# GateCVBooster.net
KiCad netlist of a schematic drawn in EAGLE
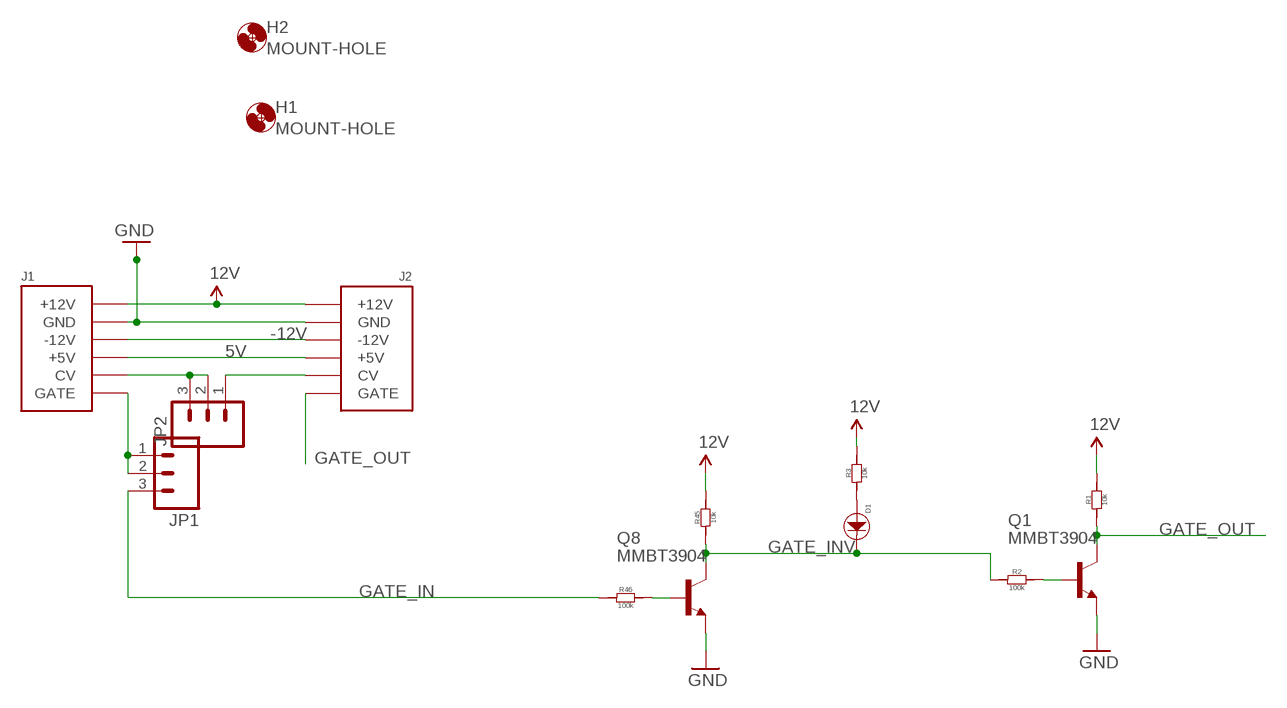
[diagram p0: schematic, sheet 1]

(export (version "E")
  (design (tool "Eeschema 10.0.6"))
  (components
    (comp (ref "D1")
      (value "LED")
      (footprint "eagle-import:LED0603")
      (libsource (lib "eagle-import") (part "LED"))
    )
    (comp (ref "H1")
      (value "MOUNT-HOLE")
      (footprint "eagle-import:3.2-NOMARKINGS-SMALLSAFEZONE")
      (libsource (lib "eagle-import") (part "MOUNT-HOLE"))
    )
    (comp (ref "H2")
      (value "MOUNT-HOLE")
      (footprint "eagle-import:3.2-NOMARKINGS-SMALLSAFEZONE")
      (libsource (lib "eagle-import") (part "MOUNT-HOLE"))
    )
    (comp (ref "J1")
      (value "POWERSHROUDED")
      (footprint "eagle-import:POWER_16_SHROUDED")
      (libsource (lib "eagle-import") (part "POWERSHROUDED"))
    )
    (comp (ref "J2")
      (value "POWER_SHROUDED_NOTEXT")
      (footprint "eagle-import:POWER_16_SHROUDED_NOTEXT")
      (libsource (lib "eagle-import") (part "POWER_SHROUDED_NOTEXT"))
    )
    (comp (ref "JP1")
      (value "M03PTH")
      (footprint "eagle-import:1X03")
      (libsource (lib "eagle-import") (part "M03PTH"))
    )
    (comp (ref "JP2")
      (value "M03PTH")
      (footprint "eagle-import:1X03")
      (libsource (lib "eagle-import") (part "M03PTH"))
    )
    (comp (ref "Q1")
      (value "MMBT3904")
      (footprint "eagle-import:SOT23-BEC")
      (fields (field (name "MF") "NXP") (field (name "MPN") "PMBT3904,215"))
      (libsource (lib "eagle-import") (part "-NPN-SOT23-BECMMBT3904LT1"))
    )
    (comp (ref "Q8")
      (value "MMBT3904")
      (footprint "eagle-import:SOT23-BEC")
      (fields (field (name "MF") "NXP") (field (name "MPN") "PMBT3904,215"))
      (libsource (lib "eagle-import") (part "-NPN-SOT23-BECMMBT3904LT1"))
    )
    (comp (ref "R1")
      (value "10k")
      (footprint "eagle-import:R0603")
      (libsource (lib "eagle-import") (part "R-0603"))
    )
    (comp (ref "R2")
      (value "100k")
      (footprint "eagle-import:R0603")
      (libsource (lib "eagle-import") (part "R-0603"))
    )
    (comp (ref "R3")
      (value "10k")
      (footprint "eagle-import:R0603")
      (libsource (lib "eagle-import") (part "R-0603"))
    )
    (comp (ref "R45")
      (value "10k")
      (footprint "eagle-import:R0603")
      (libsource (lib "eagle-import") (part "R-0603"))
    )
    (comp (ref "R46")
      (value "100k")
      (footprint "eagle-import:R0603")
      (libsource (lib "eagle-import") (part "R-0603"))
    )
  )
  (nets
    (net (code "1") (name "/-12V") (class "Default")
      (node (ref "J1") (pin "1") (pinfunction "-12V_1") (pintype "bidirectional"))
      (node (ref "J1") (pin "2") (pinfunction "-12V_2") (pintype "bidirectional"))
      (node (ref "J2") (pin "1") (pinfunction "-12V_1") (pintype "bidirectional"))
      (node (ref "J2") (pin "2") (pinfunction "-12V_2") (pintype "bidirectional"))
    )
    (net (code "2") (name "/5V") (class "Default")
      (node (ref "J1") (pin "11") (pinfunction "+5V_11") (pintype "bidirectional"))
      (node (ref "J1") (pin "12") (pinfunction "+5V_12") (pintype "bidirectional"))
      (node (ref "J2") (pin "11") (pinfunction "+5V_11") (pintype "bidirectional"))
      (node (ref "J2") (pin "12") (pinfunction "+5V_12") (pintype "bidirectional"))
    )
    (net (code "3") (name "/GATE_IN") (class "Default")
      (node (ref "JP1") (pin "3") (pinfunction "3_3") (pintype "passive"))
      (node (ref "R46") (pin "1") (pinfunction "1_1") (pintype "bidirectional"))
    )
    (net (code "4") (name "/GATE_INV") (class "Default")
      (node (ref "D1") (pin "-") (pinfunction "-_-") (pintype "passive"))
      (node (ref "Q8") (pin "C") (pinfunction "C_C") (pintype "passive"))
      (node (ref "R2") (pin "1") (pinfunction "1_1") (pintype "bidirectional"))
      (node (ref "R45") (pin "1") (pinfunction "1_1") (pintype "bidirectional"))
    )
    (net (code "5") (name "/GATE_OUT") (class "Default")
      (node (ref "J2") (pin "15") (pinfunction "GATE_15") (pintype "bidirectional"))
      (node (ref "J2") (pin "16") (pinfunction "GATE_16") (pintype "bidirectional"))
      (node (ref "Q1") (pin "C") (pinfunction "C_C") (pintype "passive"))
      (node (ref "R1") (pin "1") (pinfunction "1_1") (pintype "bidirectional"))
    )
    (net (code "6") (name "12V") (class "Default")
      (node (ref "J1") (pin "10") (pinfunction "+12V_10") (pintype "bidirectional"))
      (node (ref "J1") (pin "9") (pinfunction "+12V_9") (pintype "bidirectional"))
      (node (ref "J2") (pin "10") (pinfunction "+12V_10") (pintype "bidirectional"))
      (node (ref "J2") (pin "9") (pinfunction "+12V_9") (pintype "bidirectional"))
      (node (ref "R1") (pin "2") (pinfunction "2_2") (pintype "bidirectional"))
      (node (ref "R3") (pin "2") (pinfunction "2_2") (pintype "bidirectional"))
      (node (ref "R45") (pin "2") (pinfunction "2_2") (pintype "bidirectional"))
    )
    (net (code "7") (name "GND") (class "Default")
      (node (ref "J1") (pin "3") (pinfunction "GND_3") (pintype "bidirectional"))
      (node (ref "J1") (pin "4") (pinfunction "GND_4") (pintype "bidirectional"))
      (node (ref "J1") (pin "5") (pinfunction "GND_5") (pintype "bidirectional"))
      (node (ref "J1") (pin "6") (pinfunction "GND_6") (pintype "bidirectional"))
      (node (ref "J1") (pin "7") (pinfunction "GND_7") (pintype "bidirectional"))
      (node (ref "J1") (pin "8") (pinfunction "GND_8") (pintype "bidirectional"))
      (node (ref "J2") (pin "3") (pinfunction "GND_3") (pintype "bidirectional"))
      (node (ref "J2") (pin "4") (pinfunction "GND_4") (pintype "bidirectional"))
      (node (ref "J2") (pin "5") (pinfunction "GND_5") (pintype "bidirectional"))
      (node (ref "J2") (pin "6") (pinfunction "GND_6") (pintype "bidirectional"))
      (node (ref "J2") (pin "7") (pinfunction "GND_7") (pintype "bidirectional"))
      (node (ref "J2") (pin "8") (pinfunction "GND_8") (pintype "bidirectional"))
      (node (ref "Q1") (pin "E") (pinfunction "E_E") (pintype "passive"))
      (node (ref "Q8") (pin "E") (pinfunction "E_E") (pintype "passive"))
    )
    (net (code "8") (name "Net-(D1-Pad+)") (class "Default")
      (node (ref "D1") (pin "+") (pinfunction "+_+") (pintype "passive"))
      (node (ref "R3") (pin "1") (pinfunction "1_1") (pintype "bidirectional"))
    )
    (net (code "9") (name "Net-(J1-CV-Pad13)") (class "Default")
      (node (ref "J1") (pin "13") (pinfunction "CV_13") (pintype "bidirectional"))
      (node (ref "J1") (pin "14") (pinfunction "CV_14") (pintype "bidirectional"))
      (node (ref "JP2") (pin "2") (pinfunction "2_2") (pintype "passive"))
      (node (ref "JP2") (pin "3") (pinfunction "3_3") (pintype "passive"))
    )
    (net (code "10") (name "Net-(J1-GATE-Pad15)") (class "Default")
      (node (ref "J1") (pin "15") (pinfunction "GATE_15") (pintype "bidirectional"))
      (node (ref "J1") (pin "16") (pinfunction "GATE_16") (pintype "bidirectional"))
      (node (ref "JP1") (pin "1") (pinfunction "1_1") (pintype "passive"))
      (node (ref "JP1") (pin "2") (pinfunction "2_2") (pintype "passive"))
    )
    (net (code "11") (name "Net-(J2-CV-Pad13)") (class "Default")
      (node (ref "J2") (pin "13") (pinfunction "CV_13") (pintype "bidirectional"))
      (node (ref "J2") (pin "14") (pinfunction "CV_14") (pintype "bidirectional"))
      (node (ref "JP2") (pin "1") (pinfunction "1_1") (pintype "passive"))
    )
    (net (code "12") (name "Net-(Q1-PadB)") (class "Default")
      (node (ref "Q1") (pin "B") (pinfunction "B_B") (pintype "passive"))
      (node (ref "R2") (pin "2") (pinfunction "2_2") (pintype "bidirectional"))
    )
    (net (code "13") (name "Net-(Q8-PadB)") (class "Default")
      (node (ref "Q8") (pin "B") (pinfunction "B_B") (pintype "passive"))
      (node (ref "R46") (pin "2") (pinfunction "2_2") (pintype "bidirectional"))
    )
  )
)
